# JTAG_Trace.net
KiCad netlist of a schematic drawn in Altium Designer
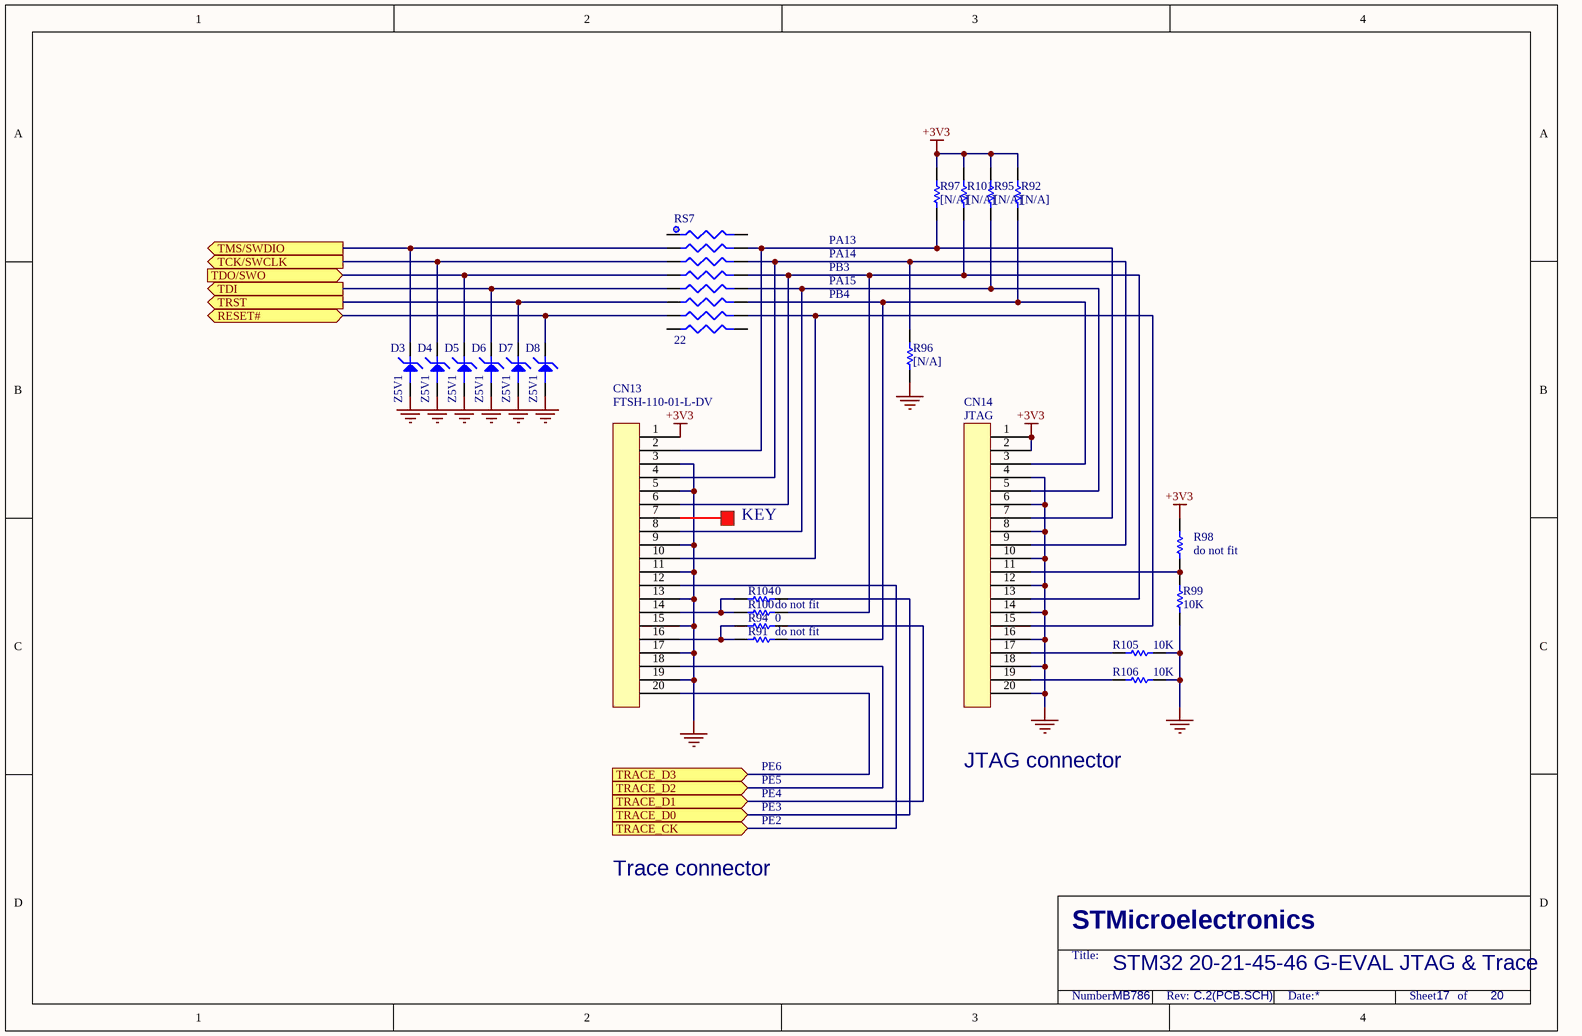
[diagram p0: JTAG&Trace.SchDoc]

(export (version "E")
  (design (tool "Eeschema 10.0.6"))
  (components
    (comp (ref "CN13")
      (value "FTSH-110-01-L-DV")
      (footprint "FTSH-110-01-L-DV")
      (libsource (lib "*") (part "20PIN1"))
    )
    (comp (ref "CN14") (value "JTAG") (footprint "IDC20L") (libsource (lib "*") (part "20PIN1")))
    (comp (ref "D3") (value "Z5V1") (footprint "SOT-23") (libsource (lib "*") (part "Z5V6")))
    (comp (ref "D4") (value "Z5V1") (footprint "SOT-23") (libsource (lib "*") (part "Z5V6")))
    (comp (ref "D5") (value "Z5V1") (footprint "SOT-23") (libsource (lib "*") (part "Z5V6")))
    (comp (ref "D6") (value "Z5V1") (footprint "SOT-23") (libsource (lib "*") (part "Z5V6")))
    (comp (ref "D7") (value "Z5V1") (footprint "SOT-23") (libsource (lib "*") (part "Z5V6")))
    (comp (ref "D8") (value "Z5V1") (footprint "SOT-23") (libsource (lib "*") (part "Z5V6")))
    (comp (ref "R91")
      (value "do not fit")
      (footprint "0603R")
      (description "Resistor")
      (fields (field (name "PUBLISHER") "Altium Limited"))
      (libsource (lib "Miscellaneous Devices") (part "Res1"))
    )
    (comp (ref "R92")
      (value "[N/A]")
      (footprint "0603R")
      (description "Resistor")
      (fields (field (name "PUBLISHER") "Altium Limited"))
      (libsource (lib "Miscellaneous Devices") (part "Res1"))
    )
    (comp (ref "R94")
      (value "0")
      (footprint "0603R")
      (description "Resistor")
      (fields (field (name "PUBLISHER") "Altium Limited"))
      (libsource (lib "Miscellaneous Devices") (part "Res1"))
    )
    (comp (ref "R95")
      (value "[N/A]")
      (footprint "0603R")
      (description "Resistor")
      (fields (field (name "PUBLISHER") "Altium Limited"))
      (libsource (lib "Miscellaneous Devices") (part "Res1"))
    )
    (comp (ref "R96")
      (value "[N/A]")
      (footprint "0603R")
      (description "Resistor")
      (fields (field (name "PUBLISHER") "Altium Limited"))
      (libsource (lib "Miscellaneous Devices") (part "Res1"))
    )
    (comp (ref "R97")
      (value "[N/A]")
      (footprint "0603R")
      (description "Resistor")
      (fields (field (name "PUBLISHER") "Altium Limited"))
      (libsource (lib "Miscellaneous Devices") (part "Res1"))
    )
    (comp (ref "R98")
      (value "do not fit")
      (footprint "0603R")
      (description "Resistor")
      (fields (field (name "PUBLISHER") "Altium Limited"))
      (libsource (lib "Miscellaneous Devices") (part "Res1"))
    )
    (comp (ref "R99")
      (value "10K")
      (footprint "0402R")
      (description "Resistor")
      (fields (field (name "PUBLISHER") "Altium Limited"))
      (libsource (lib "Miscellaneous Devices") (part "Res1"))
    )
    (comp (ref "R100")
      (value "do not fit")
      (footprint "0603R")
      (description "Resistor")
      (fields (field (name "PUBLISHER") "Altium Limited"))
      (libsource (lib "Miscellaneous Devices") (part "Res1"))
    )
    (comp (ref "R101")
      (value "[N/A]")
      (footprint "0603R")
      (description "Resistor")
      (fields (field (name "PUBLISHER") "Altium Limited"))
      (libsource (lib "Miscellaneous Devices") (part "Res1"))
    )
    (comp (ref "R104")
      (value "0")
      (footprint "0603R")
      (description "Resistor")
      (fields (field (name "PUBLISHER") "Altium Limited"))
      (libsource (lib "Miscellaneous Devices") (part "Res1"))
    )
    (comp (ref "R105")
      (value "10K")
      (footprint "0402R")
      (description "Resistor")
      (fields (field (name "PUBLISHER") "Altium Limited"))
      (libsource (lib "Miscellaneous Devices") (part "Res1"))
    )
    (comp (ref "R106")
      (value "10K")
      (footprint "0402R")
      (description "Resistor")
      (fields (field (name "PUBLISHER") "Altium Limited"))
      (libsource (lib "Miscellaneous Devices") (part "Res1"))
    )
    (comp (ref "RS7") (value "22") (footprint "RES8B_0402") (libsource (lib "*") (part "RES8B")))
  )
  (nets
    (net (code "1") (name "+3V3") (class "Default")
      (node (ref "CN13") (pin "1") (pintype "passive"))
      (node (ref "CN14") (pin "1") (pintype "passive"))
      (node (ref "CN14") (pin "2") (pintype "passive"))
      (node (ref "R101") (pin "2") (pinfunction "2_2") (pintype "passive"))
      (node (ref "R92") (pin "2") (pinfunction "2_2") (pintype "passive"))
      (node (ref "R95") (pin "2") (pinfunction "2_2") (pintype "passive"))
      (node (ref "R97") (pin "2") (pinfunction "2_2") (pintype "passive"))
      (node (ref "R98") (pin "2") (pinfunction "2_2") (pintype "passive"))
    )
    (net (code "2") (name "/RESET#") (class "Default")
      (node (ref "D8") (pin "3") (pintype "passive"))
      (node (ref "RS7") (pin "13") (pintype "passive"))
    )
    (net (code "3") (name "/TCK{slash}SWCLK") (class "Default")
      (node (ref "D4") (pin "3") (pintype "passive"))
      (node (ref "RS7") (pin "5") (pintype "passive"))
    )
    (net (code "4") (name "/TDI") (class "Default")
      (node (ref "D6") (pin "3") (pintype "passive"))
      (node (ref "RS7") (pin "9") (pintype "passive"))
    )
    (net (code "5") (name "/TDO{slash}SWO") (class "Default")
      (node (ref "D5") (pin "3") (pintype "passive"))
      (node (ref "RS7") (pin "7") (pintype "passive"))
    )
    (net (code "6") (name "/TMS{slash}SWDIO") (class "Default")
      (node (ref "D3") (pin "3") (pintype "passive"))
      (node (ref "RS7") (pin "3") (pintype "passive"))
    )
    (net (code "7") (name "/TRACE_CK") (class "Default") (node (ref "CN13") (pin "12") (pintype "passive")))
    (net (code "8") (name "/TRACE_D0") (class "Default")
      (node (ref "R104") (pin "2") (pinfunction "2_2") (pintype "passive"))
    )
    (net (code "9") (name "/TRACE_D1") (class "Default")
      (node (ref "R94") (pin "2") (pinfunction "2_2") (pintype "passive"))
    )
    (net (code "10") (name "/TRACE_D2") (class "Default") (node (ref "CN13") (pin "18") (pintype "passive")))
    (net (code "11") (name "/TRACE_D3") (class "Default") (node (ref "CN13") (pin "20") (pintype "passive")))
    (net (code "12") (name "/TRST") (class "Default")
      (node (ref "D7") (pin "3") (pintype "passive"))
      (node (ref "RS7") (pin "11") (pintype "passive"))
    )
    (net (code "13") (name "GND") (class "Default")
      (node (ref "CN13") (pin "11") (pintype "passive"))
      (node (ref "CN13") (pin "13") (pintype "passive"))
      (node (ref "CN13") (pin "15") (pintype "passive"))
      (node (ref "CN13") (pin "17") (pintype "passive"))
      (node (ref "CN13") (pin "19") (pintype "passive"))
      (node (ref "CN13") (pin "3") (pintype "passive"))
      (node (ref "CN13") (pin "5") (pintype "passive"))
      (node (ref "CN13") (pin "9") (pintype "passive"))
      (node (ref "CN14") (pin "10") (pintype "passive"))
      (node (ref "CN14") (pin "12") (pintype "passive"))
      (node (ref "CN14") (pin "14") (pintype "passive"))
      (node (ref "CN14") (pin "16") (pintype "passive"))
      (node (ref "CN14") (pin "18") (pintype "passive"))
      (node (ref "CN14") (pin "20") (pintype "passive"))
      (node (ref "CN14") (pin "4") (pintype "passive"))
      (node (ref "CN14") (pin "6") (pintype "passive"))
      (node (ref "CN14") (pin "8") (pintype "passive"))
      (node (ref "D3") (pin "2") (pintype "passive"))
      (node (ref "D4") (pin "2") (pintype "passive"))
      (node (ref "D5") (pin "2") (pintype "passive"))
      (node (ref "D6") (pin "2") (pintype "passive"))
      (node (ref "D7") (pin "2") (pintype "passive"))
      (node (ref "D8") (pin "2") (pintype "passive"))
      (node (ref "R105") (pin "2") (pinfunction "2_2") (pintype "passive"))
      (node (ref "R106") (pin "2") (pinfunction "2_2") (pintype "passive"))
      (node (ref "R96") (pin "1") (pinfunction "1_1") (pintype "passive"))
      (node (ref "R99") (pin "1") (pinfunction "1_1") (pintype "passive"))
    )
    (net (code "14") (name "Net-(CN13-Pad2)") (class "Default")
      (node (ref "CN13") (pin "2") (pintype "passive"))
      (node (ref "CN14") (pin "7") (pintype "passive"))
      (node (ref "R97") (pin "1") (pinfunction "1_1") (pintype "passive"))
      (node (ref "RS7") (pin "4") (pintype "passive"))
    )
    (net (code "15") (name "Net-(CN13-Pad4)") (class "Default")
      (node (ref "CN13") (pin "4") (pintype "passive"))
      (node (ref "CN14") (pin "9") (pintype "passive"))
      (node (ref "R96") (pin "2") (pinfunction "2_2") (pintype "passive"))
      (node (ref "RS7") (pin "6") (pintype "passive"))
    )
    (net (code "16") (name "Net-(CN13-Pad6)") (class "Default")
      (node (ref "CN13") (pin "6") (pintype "passive"))
      (node (ref "CN14") (pin "13") (pintype "passive"))
      (node (ref "R100") (pin "2") (pinfunction "2_2") (pintype "passive"))
      (node (ref "R101") (pin "1") (pinfunction "1_1") (pintype "passive"))
      (node (ref "RS7") (pin "8") (pintype "passive"))
    )
    (net (code "17") (name "Net-(CN13-Pad8)") (class "Default")
      (node (ref "CN13") (pin "8") (pintype "passive"))
      (node (ref "CN14") (pin "5") (pintype "passive"))
      (node (ref "R95") (pin "1") (pinfunction "1_1") (pintype "passive"))
      (node (ref "RS7") (pin "10") (pintype "passive"))
    )
    (net (code "18") (name "Net-(CN13-Pad10)") (class "Default")
      (node (ref "CN13") (pin "10") (pintype "passive"))
      (node (ref "CN14") (pin "15") (pintype "passive"))
      (node (ref "RS7") (pin "14") (pintype "passive"))
    )
    (net (code "19") (name "Net-(CN13-Pad14)") (class "Default")
      (node (ref "CN13") (pin "14") (pintype "passive"))
      (node (ref "R100") (pin "1") (pinfunction "1_1") (pintype "passive"))
      (node (ref "R104") (pin "1") (pinfunction "1_1") (pintype "passive"))
    )
    (net (code "20") (name "Net-(CN13-Pad16)") (class "Default")
      (node (ref "CN13") (pin "16") (pintype "passive"))
      (node (ref "R91") (pin "1") (pinfunction "1_1") (pintype "passive"))
      (node (ref "R94") (pin "1") (pinfunction "1_1") (pintype "passive"))
    )
    (net (code "21") (name "Net-(CN14-Pad3)") (class "Default")
      (node (ref "CN14") (pin "3") (pintype "passive"))
      (node (ref "R91") (pin "2") (pinfunction "2_2") (pintype "passive"))
      (node (ref "R92") (pin "1") (pinfunction "1_1") (pintype "passive"))
      (node (ref "RS7") (pin "12") (pintype "passive"))
    )
    (net (code "22") (name "Net-(CN14-Pad11)") (class "Default")
      (node (ref "CN14") (pin "11") (pintype "passive"))
      (node (ref "R98") (pin "1") (pinfunction "1_1") (pintype "passive"))
      (node (ref "R99") (pin "2") (pinfunction "2_2") (pintype "passive"))
    )
    (net (code "23") (name "Net-(CN14-Pad17)") (class "Default")
      (node (ref "CN14") (pin "17") (pintype "passive"))
      (node (ref "R105") (pin "1") (pinfunction "1_1") (pintype "passive"))
    )
    (net (code "24") (name "Net-(CN14-Pad19)") (class "Default")
      (node (ref "CN14") (pin "19") (pintype "passive"))
      (node (ref "R106") (pin "1") (pinfunction "1_1") (pintype "passive"))
    )
    (net (code "25") (name "unconnected-(CN13-Pad7)") (class "Default")
      (node (ref "CN13") (pin "7") (pintype "passive"))
    )
    (net (code "26") (name "unconnected-(RS7-Pad1)") (class "Default")
      (node (ref "RS7") (pin "1") (pintype "passive"))
    )
    (net (code "27") (name "unconnected-(RS7-Pad2)") (class "Default")
      (node (ref "RS7") (pin "2") (pintype "passive"))
    )
    (net (code "28") (name "unconnected-(RS7-Pad15)") (class "Default")
      (node (ref "RS7") (pin "15") (pintype "passive"))
    )
    (net (code "29") (name "unconnected-(RS7-Pad16)") (class "Default")
      (node (ref "RS7") (pin "16") (pintype "passive"))
    )
  )
)
